# taGPS-1251.net
KiCad netlist of a schematic drawn in EAGLE
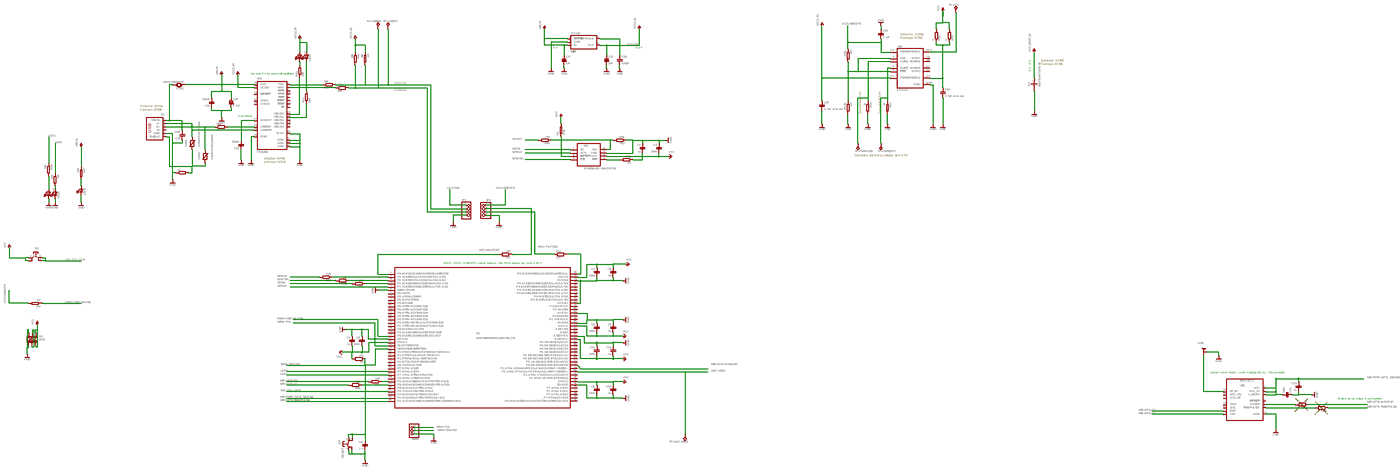
[diagram p0: schematic, sheet 1, overview]
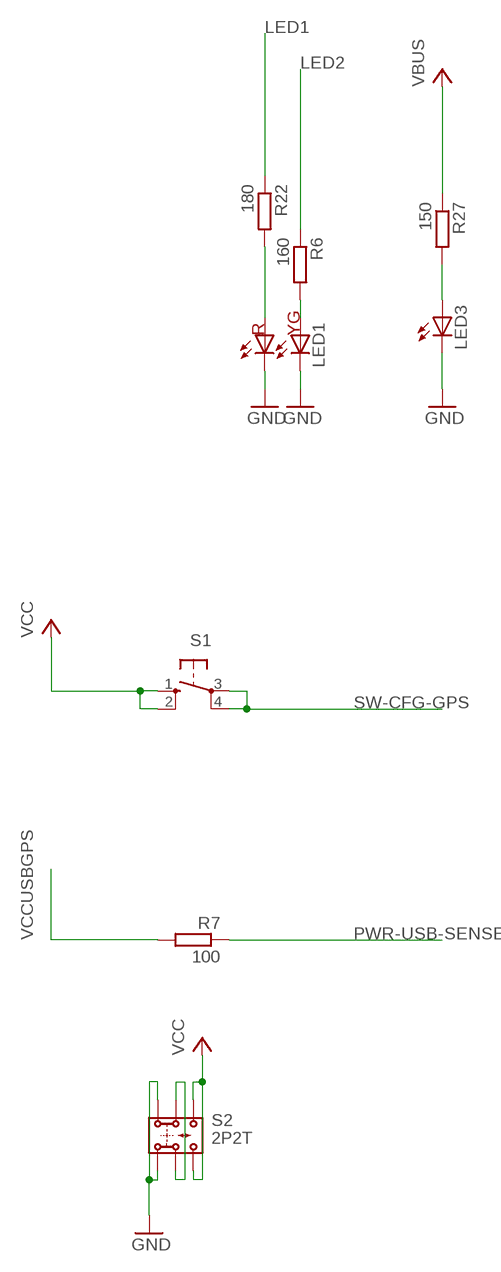
[diagram p1: schematic, sheet 1, part 1 of 4]
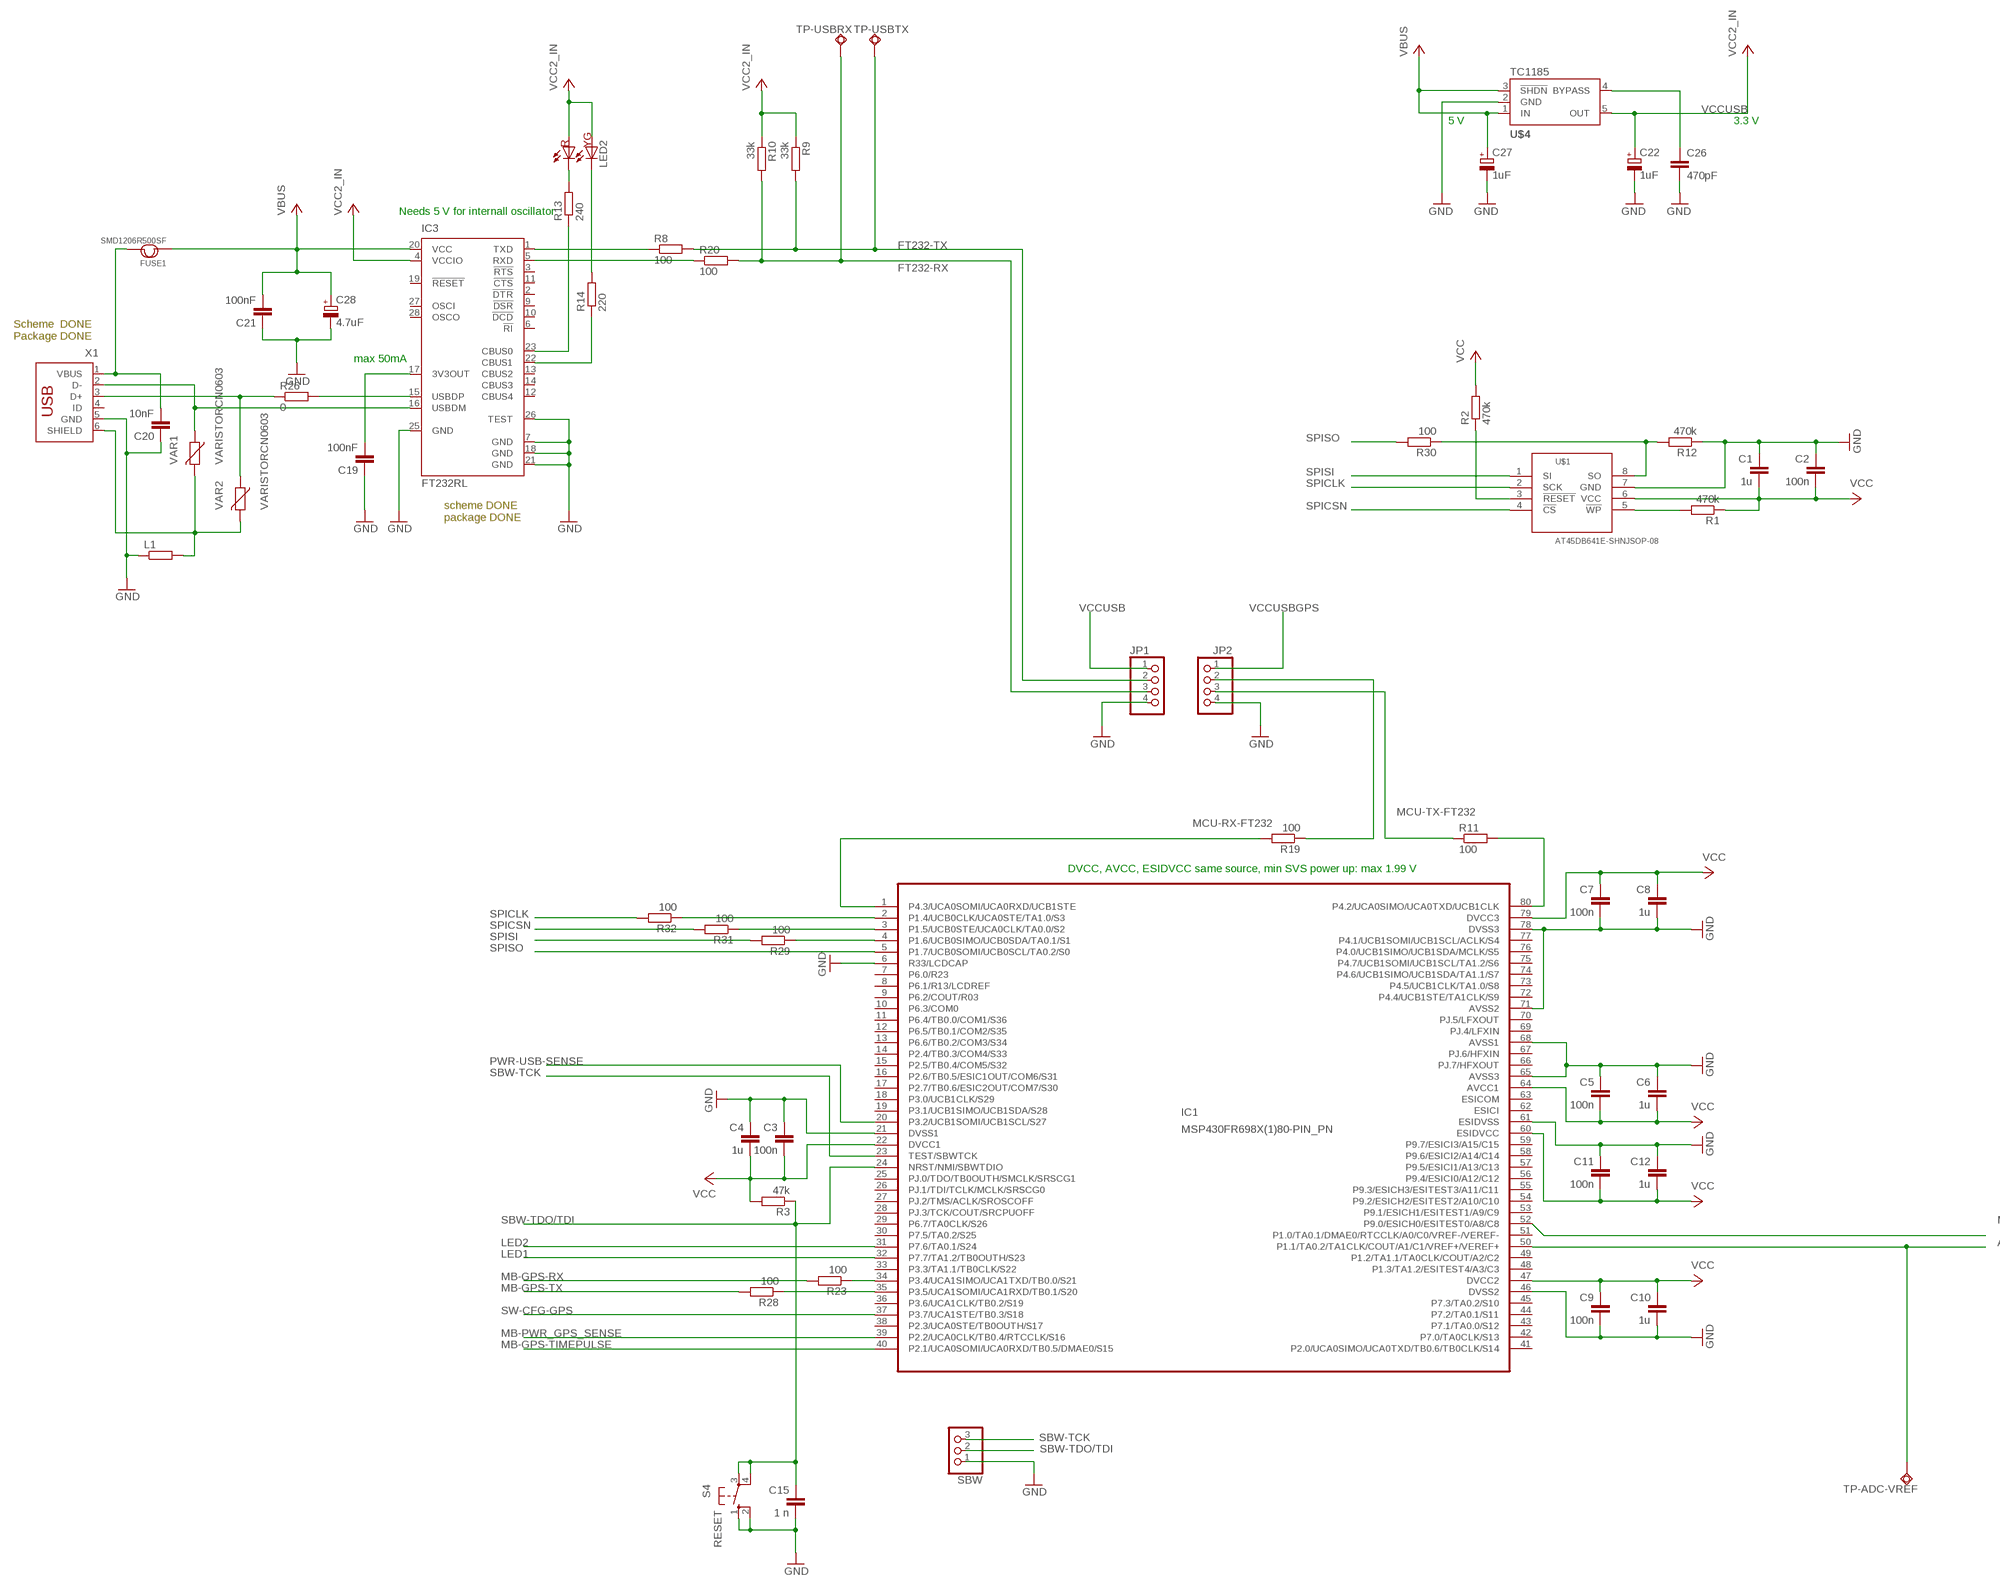
[diagram p2: schematic, sheet 1, part 2 of 4]
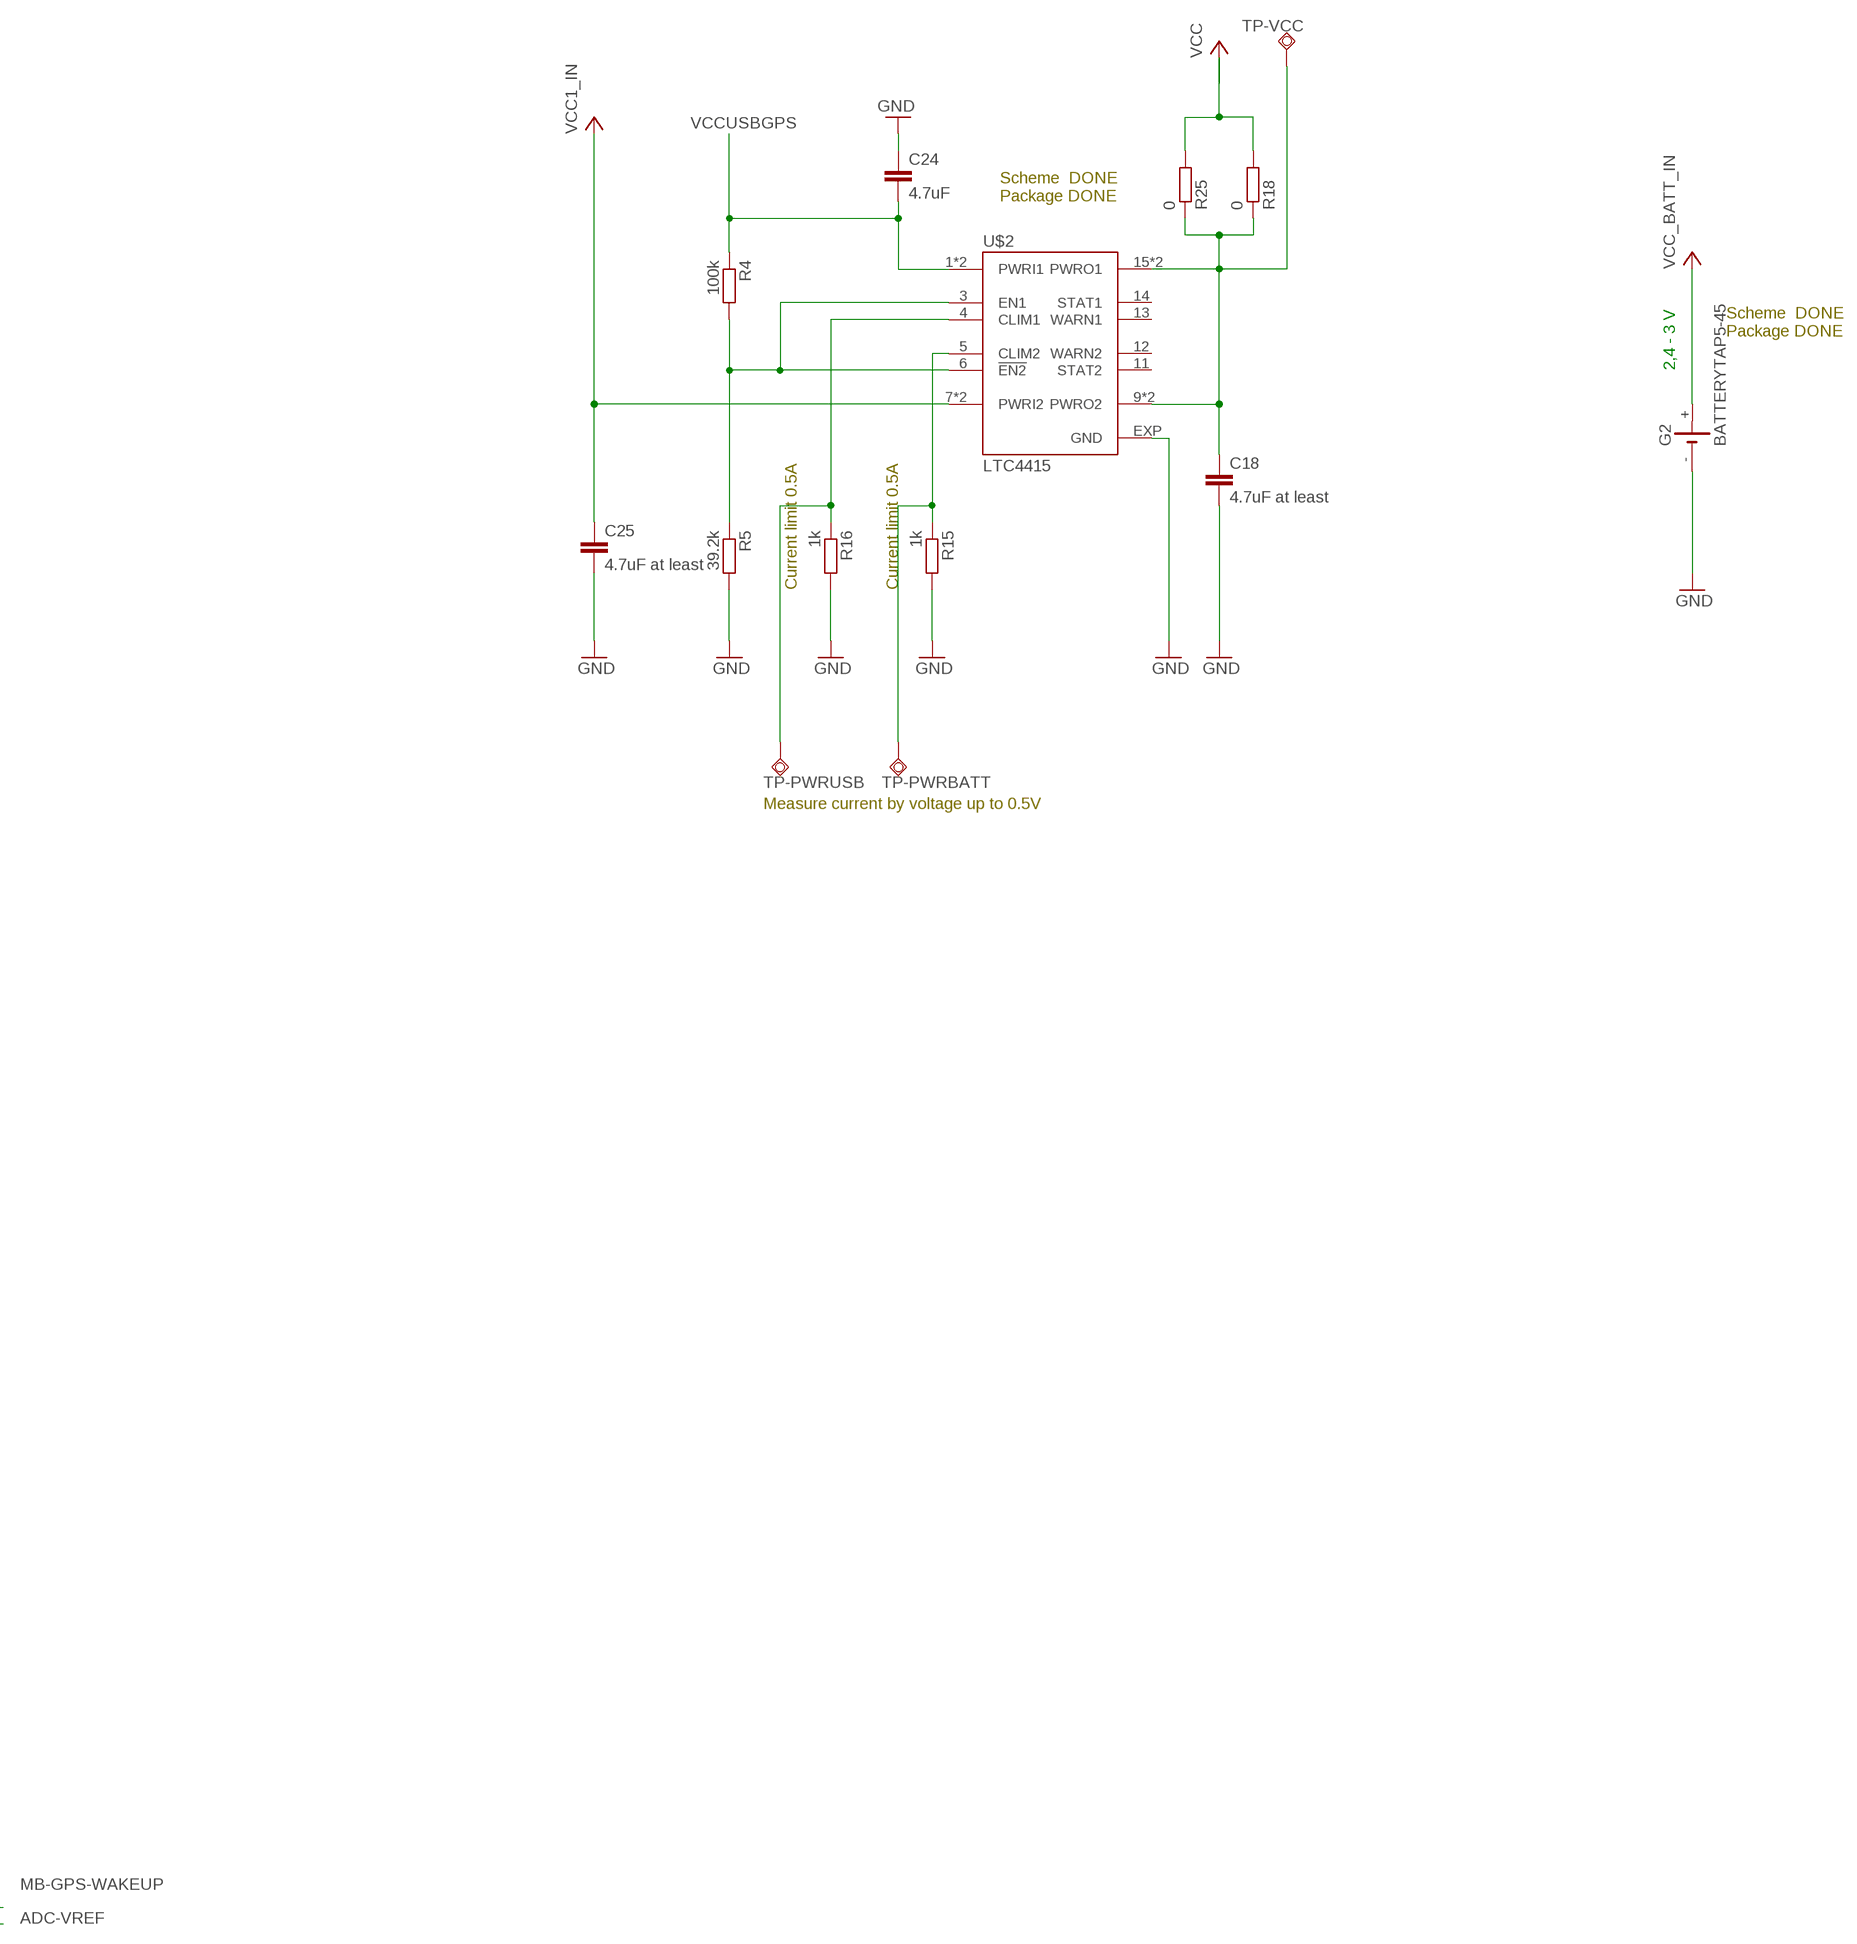
[diagram p3: schematic, sheet 1, part 3 of 4]
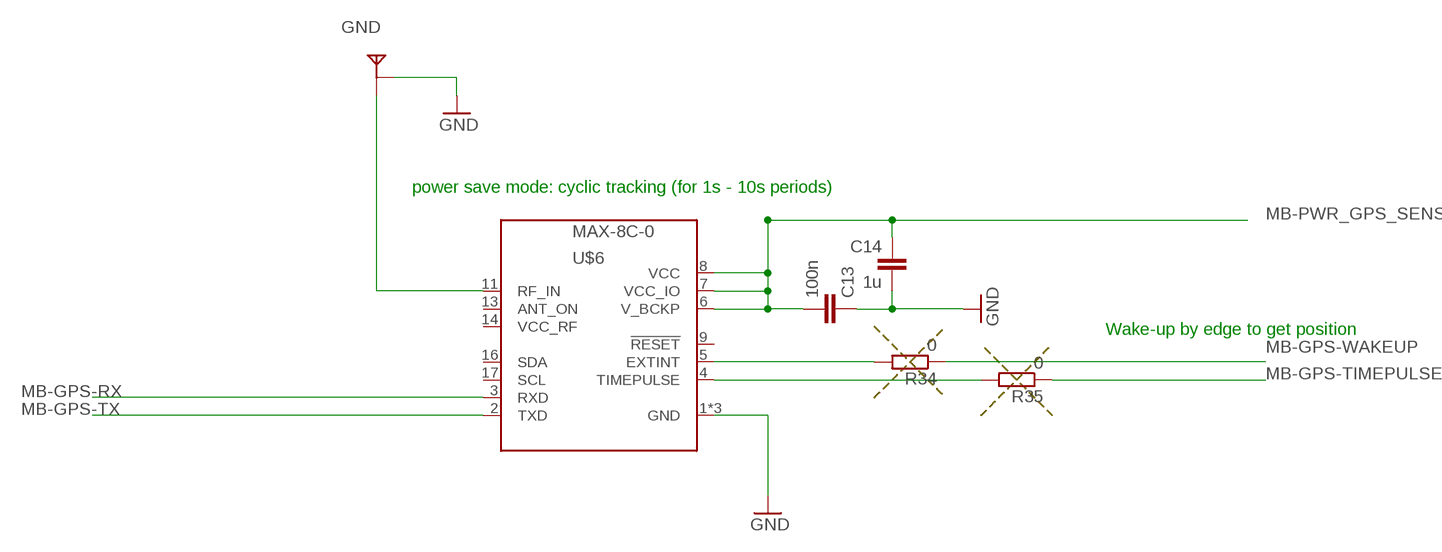
[diagram p4: schematic, sheet 1, part 4 of 4]

(export (version "E")
  (design (tool "Eeschema 10.0.6"))
  (components
    (comp (ref "C1")
      (value "1u")
      (footprint "eagle-import:C0603")
      (libsource (lib "eagle-import") (part "C-EUC0603"))
    )
    (comp (ref "C2")
      (value "100n")
      (footprint "eagle-import:C0603")
      (libsource (lib "eagle-import") (part "C-EUC0603"))
    )
    (comp (ref "C3")
      (value "100n")
      (footprint "eagle-import:C0603")
      (libsource (lib "eagle-import") (part "C-EUC0603"))
    )
    (comp (ref "C4")
      (value "1u")
      (footprint "eagle-import:C0603")
      (libsource (lib "eagle-import") (part "C-EUC0603"))
    )
    (comp (ref "C5")
      (value "100n")
      (footprint "eagle-import:C0603")
      (libsource (lib "eagle-import") (part "C-EUC0603"))
    )
    (comp (ref "C6")
      (value "1u")
      (footprint "eagle-import:C0603")
      (libsource (lib "eagle-import") (part "C-EUC0603"))
    )
    (comp (ref "C7")
      (value "100n")
      (footprint "eagle-import:C0603")
      (libsource (lib "eagle-import") (part "C-EUC0603"))
    )
    (comp (ref "C8")
      (value "1u")
      (footprint "eagle-import:C0603")
      (libsource (lib "eagle-import") (part "C-EUC0603"))
    )
    (comp (ref "C9")
      (value "100n")
      (footprint "eagle-import:C0603")
      (libsource (lib "eagle-import") (part "C-EUC0603"))
    )
    (comp (ref "C10")
      (value "1u")
      (footprint "eagle-import:C0603")
      (libsource (lib "eagle-import") (part "C-EUC0603"))
    )
    (comp (ref "C11")
      (value "100n")
      (footprint "eagle-import:C0603")
      (libsource (lib "eagle-import") (part "C-EUC0603"))
    )
    (comp (ref "C12")
      (value "1u")
      (footprint "eagle-import:C0603")
      (libsource (lib "eagle-import") (part "C-EUC0603"))
    )
    (comp (ref "C13")
      (value "100n")
      (footprint "eagle-import:C0603")
      (libsource (lib "eagle-import") (part "C-EUC0603"))
    )
    (comp (ref "C14")
      (value "1u")
      (footprint "eagle-import:C0603")
      (libsource (lib "eagle-import") (part "C-EUC0603"))
    )
    (comp (ref "C15")
      (value "1 n")
      (footprint "eagle-import:C0603")
      (libsource (lib "eagle-import") (part "C-EUC0603"))
    )
    (comp (ref "C18")
      (value "4.7uF at least")
      (footprint "eagle-import:C0805")
      (libsource (lib "eagle-import") (part "C-EUC0805"))
    )
    (comp (ref "C19")
      (value "100nF")
      (footprint "eagle-import:C0603")
      (libsource (lib "eagle-import") (part "C-EUC0603"))
    )
    (comp (ref "C20")
      (value "10nF")
      (footprint "eagle-import:C0603")
      (libsource (lib "eagle-import") (part "C-EUC0603"))
    )
    (comp (ref "C21")
      (value "100nF")
      (footprint "eagle-import:C0603")
      (libsource (lib "eagle-import") (part "C-EUC0603"))
    )
    (comp (ref "C22")
      (value "1uF")
      (footprint "eagle-import:A_3216-18W")
      (libsource (lib "eagle-import") (part "CPOL-EUA/3216-18W"))
    )
    (comp (ref "C24")
      (value "4.7uF")
      (footprint "eagle-import:C0805")
      (libsource (lib "eagle-import") (part "C-EUC0805"))
    )
    (comp (ref "C25")
      (value "4.7uF at least")
      (footprint "eagle-import:C0805")
      (libsource (lib "eagle-import") (part "C-EUC0805"))
    )
    (comp (ref "C26")
      (value "470pF")
      (footprint "eagle-import:C0603")
      (libsource (lib "eagle-import") (part "C-EUC0603"))
    )
    (comp (ref "C27")
      (value "1uF")
      (footprint "eagle-import:A_3216-18W")
      (libsource (lib "eagle-import") (part "CPOL-EUA/3216-18W"))
    )
    (comp (ref "C28")
      (value "4.7uF")
      (footprint "eagle-import:A_3216-18W")
      (libsource (lib "eagle-import") (part "CPOL-EUA/3216-18W"))
    )
    (comp (ref "FUSE1")
      (value "SMD1206R500SF")
      (footprint "eagle-import:F1812")
      (libsource (lib "eagle-import") (part "SMD-PPTC-500MA-15V(1812)"))
    )
    (comp (ref "G2")
      (value "BATTERYTAP5-45")
      (footprint "eagle-import:TAP5-45")
      (libsource (lib "eagle-import") (part "BATTERYTAP5-45"))
    )
    (comp (ref "IC1")
      (value "MSP430FR698X(1)80-PIN_PN")
      (footprint "eagle-import:PN_S-PQFP-G80")
      (libsource (lib "eagle-import") (part "MSP430FR698X(1)80-PIN_PN"))
    )
    (comp (ref "IC3")
      (value "FT232RL")
      (footprint "eagle-import:SSOP28")
      (libsource (lib "eagle-import") (part "FT232RL"))
    )
    (comp (ref "JP1")
      (value "PINHD-1X4")
      (footprint "eagle-import:1X04")
      (libsource (lib "eagle-import") (part "PINHD-1X4"))
    )
    (comp (ref "JP2")
      (value "PINHD-1X4")
      (footprint "eagle-import:1X04")
      (libsource (lib "eagle-import") (part "PINHD-1X4"))
    )
    (comp (ref "L1")
      (value "R-EU_R0603")
      (footprint "eagle-import:R0603")
      (libsource (lib "eagle-import") (part "R-EU_R0603"))
    )
    (comp (ref "LED1")
      (value "BILEDBILED")
      (footprint "eagle-import:BILED")
      (libsource (lib "eagle-import") (part "BILEDBILED"))
    )
    (comp (ref "LED2")
      (value "BILEDBILED")
      (footprint "eagle-import:BILED")
      (libsource (lib "eagle-import") (part "BILEDBILED"))
    )
    (comp (ref "LED3")
      (value "LED_E")
      (footprint "eagle-import:LED_KINGBRIGHT0603")
      (libsource (lib "eagle-import") (part "LED_E"))
    )
    (comp (ref "R1")
      (value "470k")
      (footprint "eagle-import:R0603")
      (libsource (lib "eagle-import") (part "R-EU_R0603"))
    )
    (comp (ref "R2")
      (value "470k")
      (footprint "eagle-import:R0603")
      (libsource (lib "eagle-import") (part "R-EU_R0603"))
    )
    (comp (ref "R3")
      (value "47k")
      (footprint "eagle-import:R0603")
      (libsource (lib "eagle-import") (part "R-EU_R0603"))
    )
    (comp (ref "R4")
      (value "100k")
      (footprint "eagle-import:R0603")
      (libsource (lib "eagle-import") (part "R-EU_R0603"))
    )
    (comp (ref "R5")
      (value "39.2k")
      (footprint "eagle-import:R0603")
      (libsource (lib "eagle-import") (part "R-EU_R0603"))
    )
    (comp (ref "R6")
      (value "160")
      (footprint "eagle-import:R0603")
      (libsource (lib "eagle-import") (part "R-EU_R0603"))
    )
    (comp (ref "R7")
      (value "100")
      (footprint "eagle-import:R0603")
      (libsource (lib "eagle-import") (part "R-EU_R0603"))
    )
    (comp (ref "R8")
      (value "100")
      (footprint "eagle-import:R0603")
      (libsource (lib "eagle-import") (part "R-EU_R0603"))
    )
    (comp (ref "R9")
      (value "33k")
      (footprint "eagle-import:R0603")
      (libsource (lib "eagle-import") (part "R-EU_R0603"))
    )
    (comp (ref "R10")
      (value "33k")
      (footprint "eagle-import:R0603")
      (libsource (lib "eagle-import") (part "R-EU_R0603"))
    )
    (comp (ref "R11")
      (value "100")
      (footprint "eagle-import:R0603")
      (libsource (lib "eagle-import") (part "R-EU_R0603"))
    )
    (comp (ref "R12")
      (value "470k")
      (footprint "eagle-import:R0603")
      (libsource (lib "eagle-import") (part "R-EU_R0603"))
    )
    (comp (ref "R13")
      (value "240")
      (footprint "eagle-import:R0603")
      (libsource (lib "eagle-import") (part "R-EU_R0603"))
    )
    (comp (ref "R14")
      (value "220")
      (footprint "eagle-import:R0603")
      (libsource (lib "eagle-import") (part "R-EU_R0603"))
    )
    (comp (ref "R15")
      (value "1k")
      (footprint "eagle-import:R0603")
      (libsource (lib "eagle-import") (part "R-EU_R0603"))
    )
    (comp (ref "R16")
      (value "1k")
      (footprint "eagle-import:R0603")
      (libsource (lib "eagle-import") (part "R-EU_R0603"))
    )
    (comp (ref "R18")
      (value "0")
      (footprint "eagle-import:R0603")
      (libsource (lib "eagle-import") (part "R-EU_R0603"))
    )
    (comp (ref "R19")
      (value "100")
      (footprint "eagle-import:R0603")
      (libsource (lib "eagle-import") (part "R-EU_R0603"))
    )
    (comp (ref "R20")
      (value "100")
      (footprint "eagle-import:R0603")
      (libsource (lib "eagle-import") (part "R-EU_R0603"))
    )
    (comp (ref "R22")
      (value "180")
      (footprint "eagle-import:R0603")
      (libsource (lib "eagle-import") (part "R-EU_R0603"))
    )
    (comp (ref "R23")
      (value "100")
      (footprint "eagle-import:R0603")
      (libsource (lib "eagle-import") (part "R-EU_R0603"))
    )
    (comp (ref "R25")
      (value "0")
      (footprint "eagle-import:R0603")
      (libsource (lib "eagle-import") (part "R-EU_R0603"))
    )
    (comp (ref "R26")
      (value "0")
      (footprint "eagle-import:R0603")
      (libsource (lib "eagle-import") (part "R-EU_R0603"))
    )
    (comp (ref "R27")
      (value "150")
      (footprint "eagle-import:R0603")
      (libsource (lib "eagle-import") (part "R-EU_R0603"))
    )
    (comp (ref "R28")
      (value "100")
      (footprint "eagle-import:R0603")
      (libsource (lib "eagle-import") (part "R-EU_R0603"))
    )
    (comp (ref "R29")
      (value "100")
      (footprint "eagle-import:R0603")
      (libsource (lib "eagle-import") (part "R-EU_R0603"))
    )
    (comp (ref "R30")
      (value "100")
      (footprint "eagle-import:R0603")
      (libsource (lib "eagle-import") (part "R-EU_R0603"))
    )
    (comp (ref "R31")
      (value "100")
      (footprint "eagle-import:R0603")
      (libsource (lib "eagle-import") (part "R-EU_R0603"))
    )
    (comp (ref "R32")
      (value "100")
      (footprint "eagle-import:R0603")
      (libsource (lib "eagle-import") (part "R-EU_R0603"))
    )
    (comp (ref "R34")
      (value "0")
      (footprint "eagle-import:R0603")
      (libsource (lib "eagle-import") (part "R-EU_R0603"))
    )
    (comp (ref "R35")
      (value "0")
      (footprint "eagle-import:R0603")
      (libsource (lib "eagle-import") (part "R-EU_R0603"))
    )
    (comp (ref "S1")
      (value "SWITCH-10-XX")
      (footprint "eagle-import:B3F-10XX")
      (fields (field (name "MPN") "B3F-1000"))
      (libsource (lib "eagle-import") (part "SWITCH-10-XX"))
    )
    (comp (ref "S2")
      (value "2P2T")
      (footprint "eagle-import:2P2T")
      (libsource (lib "eagle-import") (part "2P2T"))
    )
    (comp (ref "S4")
      (value "RESET")
      (footprint "eagle-import:B3F-10XX")
      (fields (field (name "MPN") "B3F-1000"))
      (libsource (lib "eagle-import") (part "SWITCH-10-XX"))
    )
    (comp (ref "SBW")
      (value "PINHD-1X3")
      (footprint "eagle-import:1X03")
      (libsource (lib "eagle-import") (part "PINHD-1X3"))
    )
    (comp (ref "TP-ADC-VREF")
      (value "TPSQTP10R")
      (footprint "eagle-import:TP10R")
      (libsource (lib "eagle-import") (part "TPSQTP10R"))
    )
    (comp (ref "TP-PWRBATT")
      (value "TPSQTP10R")
      (footprint "eagle-import:TP10R")
      (libsource (lib "eagle-import") (part "TPSQTP10R"))
    )
    (comp (ref "TP-PWRUSB")
      (value "TPSQTP10R")
      (footprint "eagle-import:TP10R")
      (libsource (lib "eagle-import") (part "TPSQTP10R"))
    )
    (comp (ref "TP-USBRX")
      (value "TPSQPAD1-13")
      (footprint "eagle-import:P1-13")
      (libsource (lib "eagle-import") (part "TPSQPAD1-13"))
    )
    (comp (ref "TP-USBTX")
      (value "TPSQPAD1-13")
      (footprint "eagle-import:P1-13")
      (libsource (lib "eagle-import") (part "TPSQPAD1-13"))
    )
    (comp (ref "TP-VCC")
      (value "TPSQPAD1-13")
      (footprint "eagle-import:P1-13")
      (libsource (lib "eagle-import") (part "TPSQPAD1-13"))
    )
    (comp (ref "U$1")
      (value "AT45DB641E-SHNJSOP-08")
      (footprint "eagle-import:JSOP-08")
      (libsource (lib "eagle-import") (part "AT45DB641E-SHNJSOP-08"))
    )
    (comp (ref "U$2")
      (value "LTC4415")
      (footprint "eagle-import:MSOP16")
      (libsource (lib "eagle-import") (part "LTC4415"))
    )
    (comp (ref "U$4")
      (value "TC1185")
      (footprint "eagle-import:SOT23-5")
      (libsource (lib "eagle-import") (part "TC1185"))
    )
    (comp (ref "U$5")
      (value "MWSL1251")
      (footprint "eagle-import:MWSL1251")
      (libsource (lib "eagle-import") (part "MWSL1251"))
    )
    (comp (ref "U$6")
      (value "MAX-8C-0")
      (footprint "eagle-import:MAX-8")
      (libsource (lib "eagle-import") (part "MAX-8C-0"))
    )
    (comp (ref "VAR1")
      (value "VARISTORCN0603")
      (footprint "eagle-import:CT_CN0603")
      (libsource (lib "eagle-import") (part "VARISTORCN0603"))
    )
    (comp (ref "VAR2")
      (value "VARISTORCN0603")
      (footprint "eagle-import:CT_CN0603")
      (libsource (lib "eagle-import") (part "VARISTORCN0603"))
    )
    (comp (ref "X1")
      (value "USB-787616")
      (footprint "eagle-import:USB")
      (libsource (lib "eagle-import") (part "USB-787616"))
    )
  )
  (nets
    (net (code "1") (name "/ADC-VREF") (class "Default")
      (node (ref "IC1") (pin "50") (pinfunction "P1.1/TA0.2/TA1CLK/COUT/A1/C1/VREF+/VEREF+_50") (pintype "bidirectional"))
      (node (ref "TP-ADC-VREF") (pin "TP") (pinfunction "TP_TP") (pintype "input"))
    )
    (net (code "2") (name "/FT232-RX") (class "Default")
      (node (ref "JP1") (pin "3") (pinfunction "3_3") (pintype "passive"))
      (node (ref "R10") (pin "2") (pinfunction "2_2") (pintype "passive"))
      (node (ref "R20") (pin "2") (pinfunction "2_2") (pintype "passive"))
      (node (ref "TP-USBRX") (pin "TP") (pinfunction "TP_TP") (pintype "input"))
    )
    (net (code "3") (name "/FT232-TX") (class "Default")
      (node (ref "JP1") (pin "2") (pinfunction "2_2") (pintype "passive"))
      (node (ref "R8") (pin "2") (pinfunction "2_2") (pintype "passive"))
      (node (ref "R9") (pin "2") (pinfunction "2_2") (pintype "passive"))
      (node (ref "TP-USBTX") (pin "TP") (pinfunction "TP_TP") (pintype "input"))
    )
    (net (code "4") (name "/LED1") (class "Default")
      (node (ref "IC1") (pin "32") (pinfunction "P7.7/TA1.2/TB0OUTH/S23_32") (pintype "bidirectional"))
      (node (ref "R22") (pin "1") (pinfunction "1_1") (pintype "passive"))
    )
    (net (code "5") (name "/LED2") (class "Default")
      (node (ref "IC1") (pin "31") (pinfunction "P7.6/TA0.1/S24_31") (pintype "bidirectional"))
      (node (ref "R6") (pin "1") (pinfunction "1_1") (pintype "passive"))
    )
    (net (code "6") (name "/MB-GPS-RX") (class "Default")
      (node (ref "R23") (pin "2") (pinfunction "2_2") (pintype "passive"))
      (node (ref "U$6") (pin "3") (pinfunction "RXD_3") (pintype "input"))
    )
    (net (code "7") (name "/MB-GPS-TIMEPULSE") (class "Default")
      (node (ref "IC1") (pin "40") (pinfunction "P2.1/UCA0SOMI/UCA0RXD/TB0.5/DMAE0/S15_40") (pintype "bidirectional"))
      (node (ref "R35") (pin "1") (pinfunction "1_1") (pintype "passive"))
    )
    (net (code "8") (name "/MB-GPS-TX") (class "Default")
      (node (ref "R28") (pin "2") (pinfunction "2_2") (pintype "passive"))
      (node (ref "U$6") (pin "2") (pinfunction "TXD_2") (pintype "output"))
    )
    (net (code "9") (name "/MB-GPS-WAKEUP") (class "Default")
      (node (ref "IC1") (pin "52") (pinfunction "P9.0/ESICH0/ESITEST0/A8/C8_52") (pintype "bidirectional"))
      (node (ref "R34") (pin "1") (pinfunction "1_1") (pintype "passive"))
    )
    (net (code "10") (name "/MB-PWR_GPS_SENSE") (class "Default")
      (node (ref "C13") (pin "2") (pinfunction "2_2") (pintype "passive"))
      (node (ref "C14") (pin "1") (pinfunction "1_1") (pintype "passive"))
      (node (ref "IC1") (pin "39") (pinfunction "P2.2/UCA0CLK/TB0.4/RTCCLK/S16_39") (pintype "bidirectional"))
      (node (ref "S2") (pin "2.1") (pinfunction "2.1_2.1") (pintype "passive"))
      (node (ref "S2") (pin "2.2") (pinfunction "2.2_2.2") (pintype "passive"))
      (node (ref "U$6") (pin "6") (pinfunction "V_BCKP_6") (pintype "power_in"))
      (node (ref "U$6") (pin "7") (pinfunction "VCC_IO_7") (pintype "power_in"))
      (node (ref "U$6") (pin "8") (pinfunction "VCC_8") (pintype "power_in"))
    )
    (net (code "11") (name "/MCU-RX-FT232") (class "Default")
      (node (ref "IC1") (pin "1") (pinfunction "P4.3/UCA0SOMI/UCA0RXD/UCB1STE_1") (pintype "bidirectional"))
      (node (ref "R19") (pin "2") (pinfunction "2_2") (pintype "passive"))
    )
    (net (code "12") (name "/MCU-TX-FT232") (class "Default")
      (node (ref "JP2") (pin "3") (pinfunction "3_3") (pintype "passive"))
      (node (ref "R11") (pin "1") (pinfunction "1_1") (pintype "passive"))
    )
    (net (code "13") (name "/PWR-USB-SENSE") (class "Default")
      (node (ref "IC1") (pin "20") (pinfunction "P3.2/UCB1SOMI/UCB1SCL/S27_20") (pintype "bidirectional"))
      (node (ref "R7") (pin "1") (pinfunction "1_1") (pintype "passive"))
    )
    (net (code "14") (name "/SBW-TCK") (class "Default")
      (node (ref "IC1") (pin "23") (pinfunction "TEST/SBWTCK_23") (pintype "output"))
      (node (ref "SBW") (pin "3") (pinfunction "3_3") (pintype "passive"))
    )
    (net (code "15") (name "/SBW-TDO{slash}TDI") (class "Default")
      (node (ref "C15") (pin "1") (pinfunction "1_1") (pintype "passive"))
      (node (ref "IC1") (pin "24") (pinfunction "NRST/NMI/SBWTDIO_24") (pintype "bidirectional"))
      (node (ref "R3") (pin "1") (pinfunction "1_1") (pintype "passive"))
      (node (ref "S4") (pin "3") (pinfunction "P_3") (pintype "passive"))
      (node (ref "S4") (pin "4") (pinfunction "P1_4") (pintype "passive"))
      (node (ref "SBW") (pin "2") (pinfunction "2_2") (pintype "passive"))
    )
    (net (code "16") (name "/SPICLK") (class "Default")
      (node (ref "R32") (pin "2") (pinfunction "2_2") (pintype "passive"))
      (node (ref "U$1") (pin "2") (pinfunction "SCK_2") (pintype "input"))
    )
    (net (code "17") (name "/SPICSN") (class "Default")
      (node (ref "R31") (pin "2") (pinfunction "2_2") (pintype "passive"))
      (node (ref "U$1") (pin "4") (pinfunction "~{CS}_4") (pintype "input"))
    )
    (net (code "18") (name "/SPISI") (class "Default")
      (node (ref "R29") (pin "2") (pinfunction "2_2") (pintype "passive"))
      (node (ref "U$1") (pin "1") (pinfunction "SI_1") (pintype "input"))
    )
    (net (code "19") (name "/SPISO") (class "Default")
      (node (ref "IC1") (pin "5") (pinfunction "P1.7/UCB0SOMI/UCB0SCL/TA0.2/S0_5") (pintype "bidirectional"))
      (node (ref "R30") (pin "2") (pinfunction "2_2") (pintype "passive"))
    )
    (net (code "20") (name "/SW-CFG-GPS") (class "Default")
      (node (ref "IC1") (pin "37") (pinfunction "P3.7/UCA1STE/TB0.3/S18_37") (pintype "bidirectional"))
      (node (ref "S1") (pin "3") (pinfunction "P_3") (pintype "passive"))
      (node (ref "S1") (pin "4") (pinfunction "P1_4") (pintype "passive"))
    )
    (net (code "21") (name "/VCCUSBGPS") (class "Default")
      (node (ref "C24") (pin "2") (pinfunction "2_2") (pintype "passive"))
      (node (ref "JP2") (pin "1") (pinfunction "1_1") (pintype "passive"))
      (node (ref "R4") (pin "1") (pinfunction "1_1") (pintype "passive"))
      (node (ref "R7") (pin "2") (pinfunction "2_2") (pintype "passive"))
      (node (ref "U$2") (pin "1") (pinfunction "PWRI1_1") (pintype "power_in"))
      (node (ref "U$2") (pin "2") (pinfunction "PWRI1_2") (pintype "power_in"))
    )
    (net (code "22") (name "GND") (class "Default")
      (node (ref "C1") (pin "1") (pinfunction "1_1") (pintype "passive"))
      (node (ref "C10") (pin "2") (pinfunction "2_2") (pintype "passive"))
      (node (ref "C11") (pin "1") (pinfunction "1_1") (pintype "passive"))
      (node (ref "C12") (pin "1") (pinfunction "1_1") (pintype "passive"))
      (node (ref "C13") (pin "1") (pinfunction "1_1") (pintype "passive"))
      (node (ref "C14") (pin "2") (pinfunction "2_2") (pintype "passive"))
      (node (ref "C15") (pin "2") (pinfunction "2_2") (pintype "passive"))
      (node (ref "C18") (pin "2") (pinfunction "2_2") (pintype "passive"))
      (node (ref "C19") (pin "1") (pinfunction "1_1") (pintype "passive"))
      (node (ref "C2") (pin "1") (pinfunction "1_1") (pintype "passive"))
      (node (ref "C20") (pin "1") (pinfunction "1_1") (pintype "passive"))
      (node (ref "C21") (pin "1") (pinfunction "1_1") (pintype "passive"))
      (node (ref "C22") (pin "-") (pinfunction "-_-") (pintype "passive"))
      (node (ref "C24") (pin "1") (pinfunction "1_1") (pintype "passive"))
      (node (ref "C25") (pin "2") (pinfunction "2_2") (pintype "passive"))
      (node (ref "C26") (pin "2") (pinfunction "2_2") (pintype "passive"))
      (node (ref "C27") (pin "-") (pinfunction "-_-") (pintype "passive"))
      (node (ref "C28") (pin "-") (pinfunction "-_-") (pintype "passive"))
      (node (ref "C3") (pin "1") (pinfunction "1_1") (pintype "passive"))
      (node (ref "C4") (pin "1") (pinfunction "1_1") (pintype "passive"))
      (node (ref "C5") (pin "1") (pinfunction "1_1") (pintype "passive"))
      (node (ref "C6") (pin "1") (pinfunction "1_1") (pintype "passive"))
      (node (ref "C7") (pin "2") (pinfunction "2_2") (pintype "passive"))
      (node (ref "C8") (pin "2") (pinfunction "2_2") (pintype "passive"))
      (node (ref "C9") (pin "2") (pinfunction "2_2") (pintype "passive"))
      (node (ref "G2") (pin "-") (pinfunction "-_-") (pintype "passive"))
      (node (ref "IC1") (pin "21") (pinfunction "DVSS1_21") (pintype "power_in"))
      (node (ref "IC1") (pin "46") (pinfunction "DVSS2_46") (pintype "power_in"))
      (node (ref "IC1") (pin "6") (pinfunction "R33/LCDCAP_6") (pintype "bidirectional"))
      (node (ref "IC1") (pin "61") (pinfunction "ESIDVSS_61") (pintype "power_in"))
      (node (ref "IC1") (pin "65") (pinfunction "AVSS3_65") (pintype "power_in"))
      (node (ref "IC1") (pin "68") (pinfunction "AVSS1_68") (pintype "power_in"))
      (node (ref "IC1") (pin "71") (pinfunction "AVSS2_71") (pintype "power_in"))
      (node (ref "IC1") (pin "78") (pinfunction "DVSS3_78") (pintype "power_in"))
      (node (ref "IC3") (pin "18") (pinfunction "GND_18") (pintype "power_in"))
      (node (ref "IC3") (pin "21") (pinfunction "GND_21") (pintype "power_in"))
      (node (ref "IC3") (pin "25") (pinfunction "GND_25") (pintype "power_in"))
      (node (ref "IC3") (pin "26") (pinfunction "TEST_26") (pintype "input"))
      (node (ref "IC3") (pin "7") (pinfunction "GND_7") (pintype "power_in"))
      (node (ref "JP1") (pin "4") (pinfunction "4_4") (pintype "passive"))
      (node (ref "JP2") (pin "4") (pinfunction "4_4") (pintype "passive"))
      (node (ref "L1") (pin "1") (pinfunction "1_1") (pintype "passive"))
      (node (ref "LED1") (pin "1") (pinfunction "1_1") (pintype "passive"))
      (node (ref "LED1") (pin "3") (pinfunction "3_3") (pintype "passive"))
      (node (ref "LED3") (pin "C") (pinfunction "C_C") (pintype "passive"))
      (node (ref "R12") (pin "1") (pinfunction "1_1") (pintype "passive"))
      (node (ref "R15") (pin "2") (pinfunction "2_2") (pintype "passive"))
      (node (ref "R16") (pin "2") (pinfunction "2_2") (pintype "passive"))
      (node (ref "R5") (pin "2") (pinfunction "2_2") (pintype "passive"))
      (node (ref "S2") (pin "1.1") (pinfunction "1.1_1.1") (pintype "passive"))
      (node (ref "S2") (pin "1.2") (pinfunction "1.2_1.2") (pintype "passive"))
      (node (ref "S4") (pin "1") (pinfunction "S_1") (pintype "passive"))
      (node (ref "S4") (pin "2") (pinfunction "S1_2") (pintype "passive"))
      (node (ref "SBW") (pin "1") (pinfunction "1_1") (pintype "passive"))
      (node (ref "U$1") (pin "7") (pinfunction "GND_7") (pintype "power_in"))
      (node (ref "U$2") (pin "EXP") (pinfunction "GND_EXP") (pintype "power_in"))
      (node (ref "U$4") (pin "2") (pinfunction "GND_2") (pintype "power_in"))
      (node (ref "U$5") (pin "P$1") (pinfunction "GND_P$1") (pintype "power_in"))
      (node (ref "U$5") (pin "P$3") (pinfunction "GND_P$3") (pintype "power_in"))
      (node (ref "U$6") (pin "1") (pinfunction "GND_1") (pintype "power_in"))
      (node (ref "U$6") (pin "10") (pinfunction "GND_10") (pintype "power_in"))
      (node (ref "U$6") (pin "12") (pinfunction "GND_12") (pintype "power_in"))
      (node (ref "X1") (pin "5") (pinfunction "GND_5") (pintype "passive"))
    )
    (net (code "23") (name "Net-(C18-Pad1)") (class "Default")
      (node (ref "C18") (pin "1") (pinfunction "1_1") (pintype "passive"))
      (node (ref "R18") (pin "1") (pinfunction "1_1") (pintype "passive"))
      (node (ref "R25") (pin "1") (pinfunction "1_1") (pintype "passive"))
      (node (ref "TP-VCC") (pin "TP") (pinfunction "TP_TP") (pintype "input"))
      (node (ref "U$2") (pin "10") (pinfunction "PWRO2_10") (pintype "power_in"))
      (node (ref "U$2") (pin "15") (pinfunction "PWRO1_15") (pintype "power_in"))
      (node (ref "U$2") (pin "16") (pinfunction "PWRO1_16") (pintype "power_in"))
      (node (ref "U$2") (pin "9") (pinfunction "PWRO2_9") (pintype "power_in"))
    )
    (net (code "24") (name "Net-(IC1-P1.4{slash}UCB0CLK{slash}UCA0STE{slash}TA1.0{slash}S3)") (class "Default")
      (node (ref "IC1") (pin "2") (pinfunction "P1.4/UCB0CLK/UCA0STE/TA1.0/S3_2") (pintype "bidirectional"))
      (node (ref "R32") (pin "1") (pinfunction "1_1") (pintype "passive"))
    )
    (net (code "25") (name "Net-(IC1-P1.5{slash}UCB0STE{slash}UCA0CLK{slash}TA0.0{slash}S2)") (class "Default")
      (node (ref "IC1") (pin "3") (pinfunction "P1.5/UCB0STE/UCA0CLK/TA0.0/S2_3") (pintype "bidirectional"))
      (node (ref "R31") (pin "1") (pinfunction "1_1") (pintype "passive"))
    )
    (net (code "26") (name "Net-(IC1-P1.6{slash}UCB0SIMO{slash}UCB0SDA{slash}TA0.1{slash}S1)") (class "Default")
      (node (ref "IC1") (pin "4") (pinfunction "P1.6/UCB0SIMO/UCB0SDA/TA0.1/S1_4") (pintype "bidirectional"))
      (node (ref "R29") (pin "1") (pinfunction "1_1") (pintype "passive"))
    )
    (net (code "27") (name "Net-(IC1-P3.4{slash}UCA1SIMO{slash}UCA1TXD{slash}TB0.0{slash}S21)") (class "Default")
      (node (ref "IC1") (pin "34") (pinfunction "P3.4/UCA1SIMO/UCA1TXD/TB0.0/S21_34") (pintype "bidirectional"))
      (node (ref "R23") (pin "1") (pinfunction "1_1") (pintype "passive"))
    )
    (net (code "28") (name "Net-(IC1-P3.5{slash}UCA1SOMI{slash}UCA1RXD{slash}TB0.1{slash}S20)") (class "Default")
      (node (ref "IC1") (pin "35") (pinfunction "P3.5/UCA1SOMI/UCA1RXD/TB0.1/S20_35") (pintype "bidirectional"))
      (node (ref "R28") (pin "1") (pinfunction "1_1") (pintype "passive"))
    )
    (net (code "29") (name "Net-(IC1-P4.2{slash}UCA0SIMO{slash}UCA0TXD{slash}UCB1CLK)") (class "Default")
      (node (ref "IC1") (pin "80") (pinfunction "P4.2/UCA0SIMO/UCA0TXD/UCB1CLK_80") (pintype "bidirectional"))
      (node (ref "R11") (pin "2") (pinfunction "2_2") (pintype "passive"))
    )
    (net (code "30") (name "Net-(IC3-3V3OUT)") (class "Default")
      (node (ref "C19") (pin "2") (pinfunction "2_2") (pintype "passive"))
      (node (ref "IC3") (pin "17") (pinfunction "3V3OUT_17") (pintype "output"))
    )
    (net (code "31") (name "Net-(IC3-CBUS0)") (class "Default")
      (node (ref "IC3") (pin "23") (pinfunction "CBUS0_23") (pintype "bidirectional"))
      (node (ref "R13") (pin "1") (pinfunction "1_1") (pintype "passive"))
    )
    (net (code "32") (name "Net-(IC3-CBUS1)") (class "Default")
      (node (ref "IC3") (pin "22") (pinfunction "CBUS1_22") (pintype "bidirectional"))
      (node (ref "R14") (pin "1") (pinfunction "1_1") (pintype "passive"))
    )
    (net (code "33") (name "Net-(IC3-RXD)") (class "Default")
      (node (ref "IC3") (pin "5") (pinfunction "RXD_5") (pintype "input"))
      (node (ref "R20") (pin "1") (pinfunction "1_1") (pintype "passive"))
    )
    (net (code "34") (name "Net-(IC3-TXD)") (class "Default")
      (node (ref "IC3") (pin "1") (pinfunction "TXD_1") (pintype "output"))
      (node (ref "R8") (pin "1") (pinfunction "1_1") (pintype "passive"))
    )
    (net (code "35") (name "Net-(IC3-USBDM)") (class "Default")
      (node (ref "IC3") (pin "16") (pinfunction "USBDM_16") (pintype "bidirectional"))
      (node (ref "VAR1") (pin "1") (pinfunction "1_1") (pintype "passive"))
      (node (ref "X1") (pin "2") (pinfunction "D-_2") (pintype "passive"))
    )
    (net (code "36") (name "Net-(IC3-USBDP)") (class "Default")
      (node (ref "IC3") (pin "15") (pinfunction "USBDP_15") (pintype "bidirectional"))
      (node (ref "R26") (pin "2") (pinfunction "2_2") (pintype "passive"))
    )
    (net (code "37") (name "Net-(JP2-Pad2)") (class "Default")
      (node (ref "JP2") (pin "2") (pinfunction "2_2") (pintype "passive"))
      (node (ref "R19") (pin "1") (pinfunction "1_1") (pintype "passive"))
    )
    (net (code "38") (name "Net-(LED1-Pad2)") (class "Default")
      (node (ref "LED1") (pin "2") (pinfunction "2_2") (pintype "passive"))
      (node (ref "R22") (pin "2") (pinfunction "2_2") (pintype "passive"))
    )
    (net (code "39") (name "Net-(LED1-Pad4)") (class "Default")
      (node (ref "LED1") (pin "4") (pinfunction "4_4") (pintype "passive"))
      (node (ref "R6") (pin "2") (pinfunction "2_2") (pintype "passive"))
    )
    (net (code "40") (name "Net-(LED2-Pad1)") (class "Default")
      (node (ref "LED2") (pin "1") (pinfunction "1_1") (pintype "passive"))
      (node (ref "R13") (pin "2") (pinfunction "2_2") (pintype "passive"))
    )
    (net (code "41") (name "Net-(LED2-Pad3)") (class "Default")
      (node (ref "LED2") (pin "3") (pinfunction "3_3") (pintype "passive"))
      (node (ref "R14") (pin "2") (pinfunction "2_2") (pintype "passive"))
    )
    (net (code "42") (name "Net-(LED3-PadA)") (class "Default")
      (node (ref "LED3") (pin "A") (pinfunction "A_A") (pintype "passive"))
      (node (ref "R27") (pin "2") (pinfunction "2_2") (pintype "passive"))
    )
    (net (code "43") (name "Net-(U$1-SO)") (class "Default")
      (node (ref "R12") (pin "2") (pinfunction "2_2") (pintype "passive"))
      (node (ref "R30") (pin "1") (pinfunction "1_1") (pintype "passive"))
      (node (ref "U$1") (pin "8") (pinfunction "SO_8") (pintype "output"))
    )
    (net (code "44") (name "Net-(U$1-~{RESET})") (class "Default")
      (node (ref "R2") (pin "1") (pinfunction "1_1") (pintype "passive"))
      (node (ref "U$1") (pin "3") (pinfunction "~{RESET}_3") (pintype "input"))
    )
    (net (code "45") (name "Net-(U$1-~{WP})") (class "Default")
      (node (ref "R1") (pin "2") (pinfunction "2_2") (pintype "passive"))
      (node (ref "U$1") (pin "5") (pinfunction "~{WP}_5") (pintype "input"))
    )
    (net (code "46") (name "Net-(U$2-CLIM1)") (class "Default")
      (node (ref "R16") (pin "1") (pinfunction "1_1") (pintype "passive"))
      (node (ref "TP-PWRUSB") (pin "TP") (pinfunction "TP_TP") (pintype "input"))
      (node (ref "U$2") (pin "4") (pinfunction "CLIM1_4") (pintype "bidirectional"))
    )
    (net (code "47") (name "Net-(U$2-CLIM2)") (class "Default")
      (node (ref "R15") (pin "1") (pinfunction "1_1") (pintype "passive"))
      (node (ref "TP-PWRBATT") (pin "TP") (pinfunction "TP_TP") (pintype "input"))
      (node (ref "U$2") (pin "5") (pinfunction "CLIM2_5") (pintype "bidirectional"))
    )
    (net (code "48") (name "Net-(U$2-EN1)") (class "Default")
      (node (ref "R4") (pin "2") (pinfunction "2_2") (pintype "passive"))
      (node (ref "R5") (pin "1") (pinfunction "1_1") (pintype "passive"))
      (node (ref "U$2") (pin "3") (pinfunction "EN1_3") (pintype "input"))
      (node (ref "U$2") (pin "6") (pinfunction "~{EN2}_6") (pintype "input"))
    )
    (net (code "49") (name "Net-(U$4-BYPASS)") (class "Default")
      (node (ref "C26") (pin "1") (pinfunction "1_1") (pintype "passive"))
      (node (ref "U$4") (pin "4") (pinfunction "BYPASS_4") (pintype "passive"))
    )
    (net (code "50") (name "Net-(U$5-FEED)") (class "Default")
      (node (ref "U$5") (pin "P$2") (pinfunction "FEED_P$2") (pintype "bidirectional"))
      (node (ref "U$6") (pin "11") (pinfunction "RF_IN_11") (pintype "input"))
    )
    (net (code "51") (name "Net-(U$6-EXTINT)") (class "Default")
      (node (ref "R34") (pin "2") (pinfunction "2_2") (pintype "passive"))
      (node (ref "U$6") (pin "5") (pinfunction "EXTINT_5") (pintype "input"))
    )
    (net (code "52") (name "Net-(U$6-TIMEPULSE)") (class "Default")
      (node (ref "R35") (pin "2") (pinfunction "2_2") (pintype "passive"))
      (node (ref "U$6") (pin "4") (pinfunction "TIMEPULSE_4") (pintype "output"))
    )
    (net (code "53") (name "Net-(X1-D+)") (class "Default")
      (node (ref "R26") (pin "1") (pinfunction "1_1") (pintype "passive"))
      (node (ref "VAR2") (pin "1") (pinfunction "1_1") (pintype "passive"))
      (node (ref "X1") (pin "3") (pinfunction "D+_3") (pintype "passive"))
    )
    (net (code "54") (name "Net-(X1-SHIELD)") (class "Default")
      (node (ref "L1") (pin "2") (pinfunction "2_2") (pintype "passive"))
      (node (ref "VAR1") (pin "2") (pinfunction "2_2") (pintype "passive"))
      (node (ref "VAR2") (pin "2") (pinfunction "2_2") (pintype "passive"))
      (node (ref "X1") (pin "6") (pinfunction "SHIELD_6") (pintype "passive"))
    )
    (net (code "55") (name "Net-(X1-VBUS)") (class "Default")
      (node (ref "C20") (pin "2") (pinfunction "2_2") (pintype "passive"))
      (node (ref "FUSE1") (pin "2") (pinfunction "2_2") (pintype "bidirectional"))
      (node (ref "X1") (pin "1") (pinfunction "VBUS_1") (pintype "passive"))
    )
    (net (code "56") (name "VBUS") (class "Default")
      (node (ref "C21") (pin "2") (pinfunction "2_2") (pintype "passive"))
      (node (ref "C27") (pin "+") (pinfunction "+_+") (pintype "passive"))
      (node (ref "C28") (pin "+") (pinfunction "+_+") (pintype "passive"))
      (node (ref "FUSE1") (pin "1") (pinfunction "1_1") (pintype "bidirectional"))
      (node (ref "IC3") (pin "20") (pinfunction "VCC_20") (pintype "power_in"))
      (node (ref "R27") (pin "1") (pinfunction "1_1") (pintype "passive"))
      (node (ref "U$4") (pin "1") (pinfunction "IN_1") (pintype "power_in"))
      (node (ref "U$4") (pin "3") (pinfunction "~{SHDN}_3") (pintype "input"))
    )
    (net (code "57") (name "VCC") (class "Default")
      (node (ref "C1") (pin "2") (pinfunction "2_2") (pintype "passive"))
      (node (ref "C10") (pin "1") (pinfunction "1_1") (pintype "passive"))
      (node (ref "C11") (pin "2") (pinfunction "2_2") (pintype "passive"))
      (node (ref "C12") (pin "2") (pinfunction "2_2") (pintype "passive"))
      (node (ref "C2") (pin "2") (pinfunction "2_2") (pintype "passive"))
      (node (ref "C3") (pin "2") (pinfunction "2_2") (pintype "passive"))
      (node (ref "C4") (pin "2") (pinfunction "2_2") (pintype "passive"))
      (node (ref "C5") (pin "2") (pinfunction "2_2") (pintype "passive"))
      (node (ref "C6") (pin "2") (pinfunction "2_2") (pintype "passive"))
      (node (ref "C7") (pin "1") (pinfunction "1_1") (pintype "passive"))
      (node (ref "C8") (pin "1") (pinfunction "1_1") (pintype "passive"))
      (node (ref "C9") (pin "1") (pinfunction "1_1") (pintype "passive"))
      (node (ref "IC1") (pin "22") (pinfunction "DVCC1_22") (pintype "power_in"))
      (node (ref "IC1") (pin "47") (pinfunction "DVCC2_47") (pintype "power_in"))
      (node (ref "IC1") (pin "60") (pinfunction "ESIDVCC_60") (pintype "power_in"))
      (node (ref "IC1") (pin "64") (pinfunction "AVCC1_64") (pintype "power_in"))
      (node (ref "IC1") (pin "79") (pinfunction "DVCC3_79") (pintype "power_in"))
      (node (ref "R1") (pin "1") (pinfunction "1_1") (pintype "passive"))
      (node (ref "R18") (pin "2") (pinfunction "2_2") (pintype "passive"))
      (node (ref "R2") (pin "2") (pinfunction "2_2") (pintype "passive"))
      (node (ref "R25") (pin "2") (pinfunction "2_2") (pintype "passive"))
      (node (ref "R3") (pin "2") (pinfunction "2_2") (pintype "passive"))
      (node (ref "S1") (pin "1") (pinfunction "S_1") (pintype "passive"))
      (node (ref "S1") (pin "2") (pinfunction "S1_2") (pintype "passive"))
      (node (ref "S2") (pin "3.1") (pinfunction "3.1_3.1") (pintype "passive"))
      (node (ref "S2") (pin "3.2") (pinfunction "3.2_3.2") (pintype "passive"))
      (node (ref "U$1") (pin "6") (pinfunction "VCC_6") (pintype "power_in"))
    )
    (net (code "58") (name "VCC1_IN") (class "Default")
      (node (ref "C25") (pin "1") (pinfunction "1_1") (pintype "passive"))
      (node (ref "G2") (pin "+") (pinfunction "+_+") (pintype "passive"))
      (node (ref "U$2") (pin "7") (pinfunction "PWRI2_7") (pintype "power_in"))
      (node (ref "U$2") (pin "8") (pinfunction "PWRI2_8") (pintype "power_in"))
    )
    (net (code "59") (name "VCC2_IN") (class "Default")
      (node (ref "C22") (pin "+") (pinfunction "+_+") (pintype "passive"))
      (node (ref "IC3") (pin "4") (pinfunction "VCCIO_4") (pintype "power_in"))
      (node (ref "JP1") (pin "1") (pinfunction "1_1") (pintype "passive"))
      (node (ref "LED2") (pin "2") (pinfunction "2_2") (pintype "passive"))
      (node (ref "LED2") (pin "4") (pinfunction "4_4") (pintype "passive"))
      (node (ref "R10") (pin "1") (pinfunction "1_1") (pintype "passive"))
      (node (ref "R9") (pin "1") (pinfunction "1_1") (pintype "passive"))
      (node (ref "U$4") (pin "5") (pinfunction "OUT_5") (pintype "power_in"))
    )
    (net (code "60") (name "unconnected-(IC1-ESICI-Pad62)") (class "Default")
      (node (ref "IC1") (pin "62") (pinfunction "ESICI_62") (pintype "bidirectional"))
    )
    (net (code "61") (name "unconnected-(IC1-ESICOM-Pad63)") (class "Default")
      (node (ref "IC1") (pin "63") (pinfunction "ESICOM_63") (pintype "bidirectional"))
    )
    (net (code "62") (name "unconnected-(IC1-P1.0{slash}TA0.1{slash}DMAE0{slash}RTCCLK{slash}A0{slash}C0{slash}VREF-{slash}VEREF--Pad51)") (class "Default")
      (node (ref "IC1") (pin "51") (pinfunction "P1.0/TA0.1/DMAE0/RTCCLK/A0/C0/VREF-/VEREF-_51") (pintype "bidirectional"))
    )
    (net (code "63") (name "unconnected-(IC1-P1.2{slash}TA1.1{slash}TA0CLK{slash}COUT{slash}A2{slash}C2-Pad49)") (class "Default")
      (node (ref "IC1") (pin "49") (pinfunction "P1.2/TA1.1/TA0CLK/COUT/A2/C2_49") (pintype "bidirectional"))
    )
    (net (code "64") (name "unconnected-(IC1-P1.3{slash}TA1.2{slash}ESITEST4{slash}A3{slash}C3-Pad48)") (class "Default")
      (node (ref "IC1") (pin "48") (pinfunction "P1.3/TA1.2/ESITEST4/A3/C3_48") (pintype "bidirectional"))
    )
    (net (code "65") (name "unconnected-(IC1-P2.0{slash}UCA0SIMO{slash}UCA0TXD{slash}TB0.6{slash}TB0CLK{slash}S14-Pad41)") (class "Default")
      (node (ref "IC1") (pin "41") (pinfunction "P2.0/UCA0SIMO/UCA0TXD/TB0.6/TB0CLK/S14_41") (pintype "bidirectional"))
    )
    (net (code "66") (name "unconnected-(IC1-P2.3{slash}UCA0STE{slash}TB0OUTH{slash}S17-Pad38)") (class "Default")
      (node (ref "IC1") (pin "38") (pinfunction "P2.3/UCA0STE/TB0OUTH/S17_38") (pintype "bidirectional"))
    )
    (net (code "67") (name "unconnected-(IC1-P2.4{slash}TB0.3{slash}COM4{slash}S33-Pad14)") (class "Default")
      (node (ref "IC1") (pin "14") (pinfunction "P2.4/TB0.3/COM4/S33_14") (pintype "bidirectional"))
    )
    (net (code "68") (name "unconnected-(IC1-P2.5{slash}TB0.4{slash}COM5{slash}S32-Pad15)") (class "Default")
      (node (ref "IC1") (pin "15") (pinfunction "P2.5/TB0.4/COM5/S32_15") (pintype "bidirectional"))
    )
    (net (code "69") (name "unconnected-(IC1-P2.6{slash}TB0.5{slash}ESIC1OUT{slash}COM6{slash}S31-Pad16)") (class "Default")
      (node (ref "IC1") (pin "16") (pinfunction "P2.6/TB0.5/ESIC1OUT/COM6/S31_16") (pintype "bidirectional"))
    )
    (net (code "70") (name "unconnected-(IC1-P2.7{slash}TB0.6{slash}ESIC2OUT{slash}COM7{slash}S30-Pad17)") (class "Default")
      (node (ref "IC1") (pin "17") (pinfunction "P2.7/TB0.6/ESIC2OUT/COM7/S30_17") (pintype "bidirectional"))
    )
    (net (code "71") (name "unconnected-(IC1-P3.0{slash}UCB1CLK{slash}S29-Pad18)") (class "Default")
      (node (ref "IC1") (pin "18") (pinfunction "P3.0/UCB1CLK/S29_18") (pintype "bidirectional"))
    )
    (net (code "72") (name "unconnected-(IC1-P3.1{slash}UCB1SIMO{slash}UCB1SDA{slash}S28-Pad19)") (class "Default")
      (node (ref "IC1") (pin "19") (pinfunction "P3.1/UCB1SIMO/UCB1SDA/S28_19") (pintype "bidirectional"))
    )
    (net (code "73") (name "unconnected-(IC1-P3.3{slash}TA1.1{slash}TB0CLK{slash}S22-Pad33)") (class "Default")
      (node (ref "IC1") (pin "33") (pinfunction "P3.3/TA1.1/TB0CLK/S22_33") (pintype "bidirectional"))
    )
    (net (code "74") (name "unconnected-(IC1-P3.6{slash}UCA1CLK{slash}TB0.2{slash}S19-Pad36)") (class "Default")
      (node (ref "IC1") (pin "36") (pinfunction "P3.6/UCA1CLK/TB0.2/S19_36") (pintype "bidirectional"))
    )
    (net (code "75") (name "unconnected-(IC1-P4.0{slash}UCB1SIMO{slash}UCB1SDA{slash}MCLK{slash}S5-Pad76)") (class "Default")
      (node (ref "IC1") (pin "76") (pinfunction "P4.0/UCB1SIMO/UCB1SDA/MCLK/S5_76") (pintype "bidirectional"))
    )
    (net (code "76") (name "unconnected-(IC1-P4.1{slash}UCB1SOMI{slash}UCB1SCL{slash}ACLK{slash}S4-Pad77)") (class "Default")
      (node (ref "IC1") (pin "77") (pinfunction "P4.1/UCB1SOMI/UCB1SCL/ACLK/S4_77") (pintype "bidirectional"))
    )
    (net (code "77") (name "unconnected-(IC1-P4.4{slash}UCB1STE{slash}TA1CLK{slash}S9-Pad72)") (class "Default")
      (node (ref "IC1") (pin "72") (pinfunction "P4.4/UCB1STE/TA1CLK/S9_72") (pintype "bidirectional"))
    )
    (net (code "78") (name "unconnected-(IC1-P4.5{slash}UCB1CLK{slash}TA1.0{slash}S8-Pad73)") (class "Default")
      (node (ref "IC1") (pin "73") (pinfunction "P4.5/UCB1CLK/TA1.0/S8_73") (pintype "bidirectional"))
    )
    (net (code "79") (name "unconnected-(IC1-P4.6{slash}UCB1SIMO{slash}UCB1SDA{slash}TA1.1{slash}S7-Pad74)") (class "Default")
      (node (ref "IC1") (pin "74") (pinfunction "P4.6/UCB1SIMO/UCB1SDA/TA1.1/S7_74") (pintype "bidirectional"))
    )
    (net (code "80") (name "unconnected-(IC1-P4.7{slash}UCB1SOMI{slash}UCB1SCL{slash}TA1.2{slash}S6-Pad75)") (class "Default")
      (node (ref "IC1") (pin "75") (pinfunction "P4.7/UCB1SOMI/UCB1SCL/TA1.2/S6_75") (pintype "bidirectional"))
    )
    (net (code "81") (name "unconnected-(IC1-P6.0{slash}R23-Pad7)") (class "Default")
      (node (ref "IC1") (pin "7") (pinfunction "P6.0/R23_7") (pintype "bidirectional"))
    )
    (net (code "82") (name "unconnected-(IC1-P6.1{slash}R13{slash}LCDREF-Pad8)") (class "Default")
      (node (ref "IC1") (pin "8") (pinfunction "P6.1/R13/LCDREF_8") (pintype "bidirectional"))
    )
    (net (code "83") (name "unconnected-(IC1-P6.2{slash}COUT{slash}R03-Pad9)") (class "Default")
      (node (ref "IC1") (pin "9") (pinfunction "P6.2/COUT/R03_9") (pintype "bidirectional"))
    )
    (net (code "84") (name "unconnected-(IC1-P6.3{slash}COM0-Pad10)") (class "Default")
      (node (ref "IC1") (pin "10") (pinfunction "P6.3/COM0_10") (pintype "bidirectional"))
    )
    (net (code "85") (name "unconnected-(IC1-P6.4{slash}TB0.0{slash}COM1{slash}S36-Pad11)") (class "Default")
      (node (ref "IC1") (pin "11") (pinfunction "P6.4/TB0.0/COM1/S36_11") (pintype "bidirectional"))
    )
    (net (code "86") (name "unconnected-(IC1-P6.5{slash}TB0.1{slash}COM2{slash}S35-Pad12)") (class "Default")
      (node (ref "IC1") (pin "12") (pinfunction "P6.5/TB0.1/COM2/S35_12") (pintype "bidirectional"))
    )
    (net (code "87") (name "unconnected-(IC1-P6.6{slash}TB0.2{slash}COM3{slash}S34-Pad13)") (class "Default")
      (node (ref "IC1") (pin "13") (pinfunction "P6.6/TB0.2/COM3/S34_13") (pintype "bidirectional"))
    )
    (net (code "88") (name "unconnected-(IC1-P6.7{slash}TA0CLK{slash}S26-Pad29)") (class "Default")
      (node (ref "IC1") (pin "29") (pinfunction "P6.7/TA0CLK/S26_29") (pintype "bidirectional"))
    )
    (net (code "89") (name "unconnected-(IC1-P7.0{slash}TA0CLK{slash}S13-Pad42)") (class "Default")
      (node (ref "IC1") (pin "42") (pinfunction "P7.0/TA0CLK/S13_42") (pintype "bidirectional"))
    )
    (net (code "90") (name "unconnected-(IC1-P7.1{slash}TA0.0{slash}S12-Pad43)") (class "Default")
      (node (ref "IC1") (pin "43") (pinfunction "P7.1/TA0.0/S12_43") (pintype "bidirectional"))
    )
    (net (code "91") (name "unconnected-(IC1-P7.2{slash}TA0.1{slash}S11-Pad44)") (class "Default")
      (node (ref "IC1") (pin "44") (pinfunction "P7.2/TA0.1/S11_44") (pintype "bidirectional"))
    )
    (net (code "92") (name "unconnected-(IC1-P7.3{slash}TA0.2{slash}S10-Pad45)") (class "Default")
      (node (ref "IC1") (pin "45") (pinfunction "P7.3/TA0.2/S10_45") (pintype "bidirectional"))
    )
    (net (code "93") (name "unconnected-(IC1-P7.5{slash}TA0.2{slash}S25-Pad30)") (class "Default")
      (node (ref "IC1") (pin "30") (pinfunction "P7.5/TA0.2/S25_30") (pintype "bidirectional"))
    )
    (net (code "94") (name "unconnected-(IC1-P9.1{slash}ESICH1{slash}ESITEST1{slash}A9{slash}C9-Pad53)") (class "Default")
      (node (ref "IC1") (pin "53") (pinfunction "P9.1/ESICH1/ESITEST1/A9/C9_53") (pintype "bidirectional"))
    )
    (net (code "95") (name "unconnected-(IC1-P9.2{slash}ESICH2{slash}ESITEST2{slash}A10{slash}C10-Pad54)") (class "Default")
      (node (ref "IC1") (pin "54") (pinfunction "P9.2/ESICH2/ESITEST2/A10/C10_54") (pintype "bidirectional"))
    )
    (net (code "96") (name "unconnected-(IC1-P9.3{slash}ESICH3{slash}ESITEST3{slash}A11{slash}C11-Pad55)") (class "Default")
      (node (ref "IC1") (pin "55") (pinfunction "P9.3/ESICH3/ESITEST3/A11/C11_55") (pintype "bidirectional"))
    )
    (net (code "97") (name "unconnected-(IC1-P9.4{slash}ESICI0{slash}A12{slash}C12-Pad56)") (class "Default")
      (node (ref "IC1") (pin "56") (pinfunction "P9.4/ESICI0/A12/C12_56") (pintype "bidirectional"))
    )
    (net (code "98") (name "unconnected-(IC1-P9.5{slash}ESICI1{slash}A13{slash}C13-Pad57)") (class "Default")
      (node (ref "IC1") (pin "57") (pinfunction "P9.5/ESICI1/A13/C13_57") (pintype "bidirectional"))
    )
    (net (code "99") (name "unconnected-(IC1-P9.6{slash}ESICI2{slash}A14{slash}C14-Pad58)") (class "Default")
      (node (ref "IC1") (pin "58") (pinfunction "P9.6/ESICI2/A14/C14_58") (pintype "bidirectional"))
    )
    (net (code "100") (name "unconnected-(IC1-P9.7{slash}ESICI3{slash}A15{slash}C15-Pad59)") (class "Default")
      (node (ref "IC1") (pin "59") (pinfunction "P9.7/ESICI3/A15/C15_59") (pintype "bidirectional"))
    )
    (net (code "101") (name "unconnected-(IC1-PJ.0{slash}TDO{slash}TB0OUTH{slash}SMCLK{slash}SRSCG1-Pad25)") (class "Default")
      (node (ref "IC1") (pin "25") (pinfunction "PJ.0/TDO/TB0OUTH/SMCLK/SRSCG1_25") (pintype "bidirectional"))
    )
    (net (code "102") (name "unconnected-(IC1-PJ.1{slash}TDI{slash}TCLK{slash}MCLK{slash}SRSCG0-Pad26)") (class "Default")
      (node (ref "IC1") (pin "26") (pinfunction "PJ.1/TDI/TCLK/MCLK/SRSCG0_26") (pintype "bidirectional"))
    )
    (net (code "103") (name "unconnected-(IC1-PJ.2{slash}TMS{slash}ACLK{slash}SROSCOFF-Pad27)") (class "Default")
      (node (ref "IC1") (pin "27") (pinfunction "PJ.2/TMS/ACLK/SROSCOFF_27") (pintype "bidirectional"))
    )
    (net (code "104") (name "unconnected-(IC1-PJ.3{slash}TCK{slash}COUT{slash}SRCPUOFF-Pad28)") (class "Default")
      (node (ref "IC1") (pin "28") (pinfunction "PJ.3/TCK/COUT/SRCPUOFF_28") (pintype "bidirectional"))
    )
    (net (code "105") (name "unconnected-(IC1-PJ.4{slash}LFXIN-Pad69)") (class "Default")
      (node (ref "IC1") (pin "69") (pinfunction "PJ.4/LFXIN_69") (pintype "bidirectional"))
    )
    (net (code "106") (name "unconnected-(IC1-PJ.5{slash}LFXOUT-Pad70)") (class "Default")
      (node (ref "IC1") (pin "70") (pinfunction "PJ.5/LFXOUT_70") (pintype "bidirectional"))
    )
    (net (code "107") (name "unconnected-(IC1-PJ.6{slash}HFXIN-Pad67)") (class "Default")
      (node (ref "IC1") (pin "67") (pinfunction "PJ.6/HFXIN_67") (pintype "bidirectional"))
    )
    (net (code "108") (name "unconnected-(IC1-PJ.7{slash}HFXOUT-Pad66)") (class "Default")
      (node (ref "IC1") (pin "66") (pinfunction "PJ.7/HFXOUT_66") (pintype "bidirectional"))
    )
    (net (code "109") (name "unconnected-(IC3-CBUS2-Pad13)") (class "Default")
      (node (ref "IC3") (pin "13") (pinfunction "CBUS2_13") (pintype "bidirectional"))
    )
    (net (code "110") (name "unconnected-(IC3-CBUS3-Pad14)") (class "Default")
      (node (ref "IC3") (pin "14") (pinfunction "CBUS3_14") (pintype "bidirectional"))
    )
    (net (code "111") (name "unconnected-(IC3-CBUS4-Pad12)") (class "Default")
      (node (ref "IC3") (pin "12") (pinfunction "CBUS4_12") (pintype "bidirectional"))
    )
    (net (code "112") (name "unconnected-(IC3-OSCI-Pad27)") (class "Default")
      (node (ref "IC3") (pin "27") (pinfunction "OSCI_27") (pintype "input"))
    )
    (net (code "113") (name "unconnected-(IC3-OSCO-Pad28)") (class "Default")
      (node (ref "IC3") (pin "28") (pinfunction "OSCO_28") (pintype "output"))
    )
    (net (code "114") (name "unconnected-(IC3-~{CTS}-Pad11)") (class "Default")
      (node (ref "IC3") (pin "11") (pinfunction "~{CTS}_11") (pintype "input"))
    )
    (net (code "115") (name "unconnected-(IC3-~{DCD}-Pad10)") (class "Default")
      (node (ref "IC3") (pin "10") (pinfunction "~{DCD}_10") (pintype "input"))
    )
    (net (code "116") (name "unconnected-(IC3-~{DSR}-Pad9)") (class "Default")
      (node (ref "IC3") (pin "9") (pinfunction "~{DSR}_9") (pintype "input"))
    )
    (net (code "117") (name "unconnected-(IC3-~{DTR}-Pad2)") (class "Default")
      (node (ref "IC3") (pin "2") (pinfunction "~{DTR}_2") (pintype "output"))
    )
    (net (code "118") (name "unconnected-(IC3-~{RESET}-Pad19)") (class "Default")
      (node (ref "IC3") (pin "19") (pinfunction "~{RESET}_19") (pintype "input"))
    )
    (net (code "119") (name "unconnected-(IC3-~{RI}-Pad6)") (class "Default")
      (node (ref "IC3") (pin "6") (pinfunction "~{RI}_6") (pintype "input"))
    )
    (net (code "120") (name "unconnected-(IC3-~{RTS}-Pad3)") (class "Default")
      (node (ref "IC3") (pin "3") (pinfunction "~{RTS}_3") (pintype "output"))
    )
    (net (code "121") (name "unconnected-(U$2-STAT1-Pad14)") (class "Default")
      (node (ref "U$2") (pin "14") (pinfunction "STAT1_14") (pintype "bidirectional"))
    )
    (net (code "122") (name "unconnected-(U$2-STAT2-Pad11)") (class "Default")
      (node (ref "U$2") (pin "11") (pinfunction "STAT2_11") (pintype "bidirectional"))
    )
    (net (code "123") (name "unconnected-(U$2-WARN1-Pad13)") (class "Default")
      (node (ref "U$2") (pin "13") (pinfunction "WARN1_13") (pintype "bidirectional"))
    )
    (net (code "124") (name "unconnected-(U$2-WARN2-Pad12)") (class "Default")
      (node (ref "U$2") (pin "12") (pinfunction "WARN2_12") (pintype "bidirectional"))
    )
    (net (code "125") (name "unconnected-(U$6-ANT_ON-Pad13)") (class "Default")
      (node (ref "U$6") (pin "13") (pinfunction "ANT_ON_13") (pintype "output"))
    )
    (net (code "126") (name "unconnected-(U$6-SCL-Pad17)") (class "Default")
      (node (ref "U$6") (pin "17") (pinfunction "SCL_17") (pintype "input"))
    )
    (net (code "127") (name "unconnected-(U$6-SDA-Pad16)") (class "Default")
      (node (ref "U$6") (pin "16") (pinfunction "SDA_16") (pintype "bidirectional"))
    )
    (net (code "128") (name "unconnected-(U$6-VCC_RF-Pad14)") (class "Default")
      (node (ref "U$6") (pin "14") (pinfunction "VCC_RF_14") (pintype "output"))
    )
    (net (code "129") (name "unconnected-(U$6-~{RESET}-Pad9)") (class "Default")
      (node (ref "U$6") (pin "9") (pinfunction "~{RESET}_9") (pintype "bidirectional"))
    )
    (net (code "130") (name "unconnected-(X1-ID-Pad4)") (class "Default")
      (node (ref "X1") (pin "4") (pinfunction "ID_4") (pintype "passive"))
    )
  )
)
